# Esquematico_Amplificador.net
KiCad netlist of a schematic drawn in Altium Designer
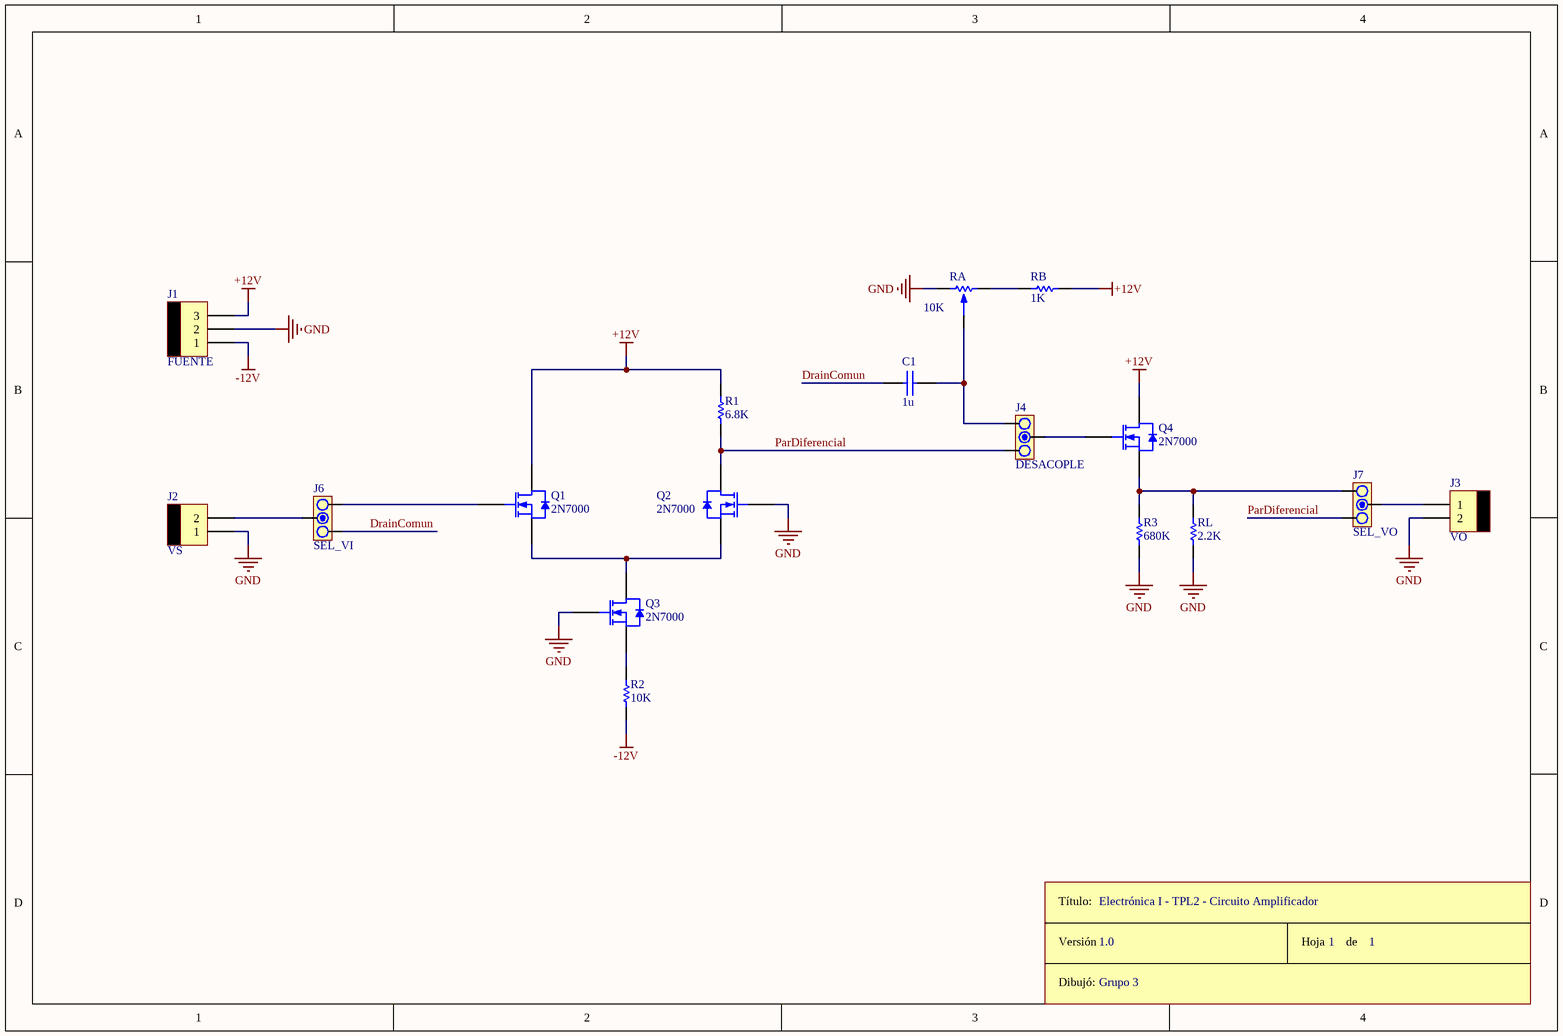
[diagram p0: Esquematico_Amplificador.SchDoc]

(export (version "E")
  (design (tool "Eeschema 10.0.6"))
  (components
    (comp (ref "C1") (value "1u") (footprint "CAP200") (libsource (lib "LIBEBAL") (part "CAP")))
    (comp (ref "J1") (value "FUENTE") (footprint "MOLEX3") (libsource (lib "LIBEBAL") (part "MOLEX3")))
    (comp (ref "J2") (value "VS") (footprint "MOLEX2") (libsource (lib "LIBEBAL") (part "MOLEX2")))
    (comp (ref "J3") (value "VO") (footprint "MOLEX2") (libsource (lib "") (part "MOLEX2_1")))
    (comp (ref "J4") (value "DESACOPLE") (footprint "JUMPER3") (libsource (lib "LIBEBAL") (part "JUMPER3")))
    (comp (ref "J6") (value "SEL_VI") (footprint "JUMPER3") (libsource (lib "") (part "JUMPER3_1")))
    (comp (ref "J7") (value "SEL_VO") (footprint "JUMPER3") (libsource (lib "LIBEBAL") (part "JUMPER3")))
    (comp (ref "Q1")
      (value "2N7000")
      (footprint "SOT54")
      (description "N-channel Enhancement Mode Field-effect Transistor")
      (fields (field (name "PUBLISHER") "Altium Limited"))
      (libsource (lib "Philips Discrete MOSFET - Low Power") (part "2N7000"))
    )
    (comp (ref "Q2")
      (value "2N7000")
      (footprint "SOT54")
      (description "N-channel Enhancement Mode Field-effect Transistor")
      (fields (field (name "PUBLISHER") "Altium Limited"))
      (libsource (lib "Philips Discrete MOSFET - Low Power") (part "2N7000"))
    )
    (comp (ref "Q3")
      (value "2N7000")
      (footprint "SOT54")
      (description "N-channel Enhancement Mode Field-effect Transistor")
      (fields (field (name "PUBLISHER") "Altium Limited"))
      (libsource (lib "Philips Discrete MOSFET - Low Power") (part "2N7000"))
    )
    (comp (ref "Q4")
      (value "2N7000")
      (footprint "SOT54")
      (description "N-channel Enhancement Mode Field-effect Transistor")
      (fields (field (name "PUBLISHER") "Altium Limited"))
      (libsource (lib "Philips Discrete MOSFET - Low Power") (part "2N7000"))
    )
    (comp (ref "R1") (value "6.8K") (footprint "RES300") (libsource (lib "LIBEBAL") (part "RES")))
    (comp (ref "R2") (value "10K") (footprint "RES300") (libsource (lib "LIBEBAL") (part "RES")))
    (comp (ref "R3") (value "680K") (footprint "RES300") (libsource (lib "LIBEBAL") (part "RES")))
    (comp (ref "RA") (value "10K") (footprint "PRESET V") (libsource (lib "LIBEBAL") (part "PRESET")))
    (comp (ref "RB") (value "1K") (footprint "RES300") (libsource (lib "LIBEBAL") (part "RES")))
    (comp (ref "RL") (value "2.2K") (footprint "RES300") (libsource (lib "LIBEBAL") (part "RES")))
    (comp (ref "ROT1") (value "Rótulo") (libsource (lib "LIB PIO IX") (part "Rótulo")))
  )
  (nets
    (net (code "1") (name "+12V") (class "Default")
      (node (ref "J1") (pin "3") (pinfunction "3_3") (pintype "passive"))
      (node (ref "Q1") (pin "1") (pinfunction "D_1") (pintype "passive"))
      (node (ref "Q4") (pin "1") (pinfunction "D_1") (pintype "passive"))
      (node (ref "R1") (pin "2") (pinfunction "2_2") (pintype "passive"))
      (node (ref "RB") (pin "1") (pinfunction "1_1") (pintype "passive"))
    )
    (net (code "2") (name "-12V") (class "Default")
      (node (ref "J1") (pin "1") (pinfunction "1_1") (pintype "passive"))
      (node (ref "R2") (pin "1") (pinfunction "1_1") (pintype "passive"))
    )
    (net (code "3") (name "/DrainComun") (class "Default")
      (node (ref "C1") (pin "1") (pinfunction "1_1") (pintype "passive"))
      (node (ref "J6") (pin "3") (pinfunction "3_3") (pintype "passive"))
    )
    (net (code "4") (name "/ParDiferencial") (class "Default")
      (node (ref "J4") (pin "1") (pinfunction "1_1") (pintype "passive"))
      (node (ref "J7") (pin "1") (pinfunction "1_1") (pintype "passive"))
      (node (ref "Q2") (pin "1") (pinfunction "D_1") (pintype "passive"))
      (node (ref "R1") (pin "1") (pinfunction "1_1") (pintype "passive"))
    )
    (net (code "5") (name "GND") (class "Default")
      (node (ref "J1") (pin "2") (pinfunction "2_2") (pintype "passive"))
      (node (ref "J2") (pin "1") (pinfunction "1_1") (pintype "passive"))
      (node (ref "J3") (pin "2") (pinfunction "2_2") (pintype "passive"))
      (node (ref "Q2") (pin "2") (pinfunction "G_2") (pintype "passive"))
      (node (ref "Q3") (pin "2") (pinfunction "G_2") (pintype "passive"))
      (node (ref "R3") (pin "1") (pinfunction "1_1") (pintype "passive"))
      (node (ref "RA") (pin "3") (pinfunction "3_3") (pintype "passive"))
      (node (ref "RL") (pin "1") (pinfunction "1_1") (pintype "passive"))
    )
    (net (code "6") (name "Net-(C1-Pad2)") (class "Default")
      (node (ref "C1") (pin "2") (pinfunction "2_2") (pintype "passive"))
      (node (ref "J4") (pin "3") (pinfunction "3_3") (pintype "passive"))
      (node (ref "RA") (pin "2") (pinfunction "2_2") (pintype "passive"))
    )
    (net (code "7") (name "Net-(J2-Pad2)") (class "Default")
      (node (ref "J2") (pin "2") (pinfunction "2_2") (pintype "passive"))
      (node (ref "J6") (pin "2") (pinfunction "2_2") (pintype "passive"))
    )
    (net (code "8") (name "Net-(J3-Pad1)") (class "Default")
      (node (ref "J3") (pin "1") (pinfunction "1_1") (pintype "passive"))
      (node (ref "J7") (pin "2") (pinfunction "2_2") (pintype "passive"))
    )
    (net (code "9") (name "Net-(Q1-G)") (class "Default")
      (node (ref "J6") (pin "1") (pinfunction "1_1") (pintype "passive"))
      (node (ref "Q1") (pin "2") (pinfunction "G_2") (pintype "passive"))
    )
    (net (code "10") (name "Net-(Q1-S)") (class "Default")
      (node (ref "Q1") (pin "3") (pinfunction "S_3") (pintype "passive"))
      (node (ref "Q2") (pin "3") (pinfunction "S_3") (pintype "passive"))
      (node (ref "Q3") (pin "1") (pinfunction "D_1") (pintype "passive"))
    )
    (net (code "11") (name "Net-(Q3-S)") (class "Default")
      (node (ref "Q3") (pin "3") (pinfunction "S_3") (pintype "passive"))
      (node (ref "R2") (pin "2") (pinfunction "2_2") (pintype "passive"))
    )
    (net (code "12") (name "Net-(Q4-G)") (class "Default")
      (node (ref "J4") (pin "2") (pinfunction "2_2") (pintype "passive"))
      (node (ref "Q4") (pin "2") (pinfunction "G_2") (pintype "passive"))
    )
    (net (code "13") (name "Net-(Q4-S)") (class "Default")
      (node (ref "J7") (pin "3") (pinfunction "3_3") (pintype "passive"))
      (node (ref "Q4") (pin "3") (pinfunction "S_3") (pintype "passive"))
      (node (ref "R3") (pin "2") (pinfunction "2_2") (pintype "passive"))
      (node (ref "RL") (pin "2") (pinfunction "2_2") (pintype "passive"))
    )
    (net (code "14") (name "Net-(RA-Pad1)") (class "Default")
      (node (ref "RA") (pin "1") (pinfunction "1_1") (pintype "passive"))
      (node (ref "RB") (pin "2") (pinfunction "2_2") (pintype "passive"))
    )
  )
)
